# 4brar07_Audio_Amplifier.net
KiCad netlist of a schematic drawn in EAGLE
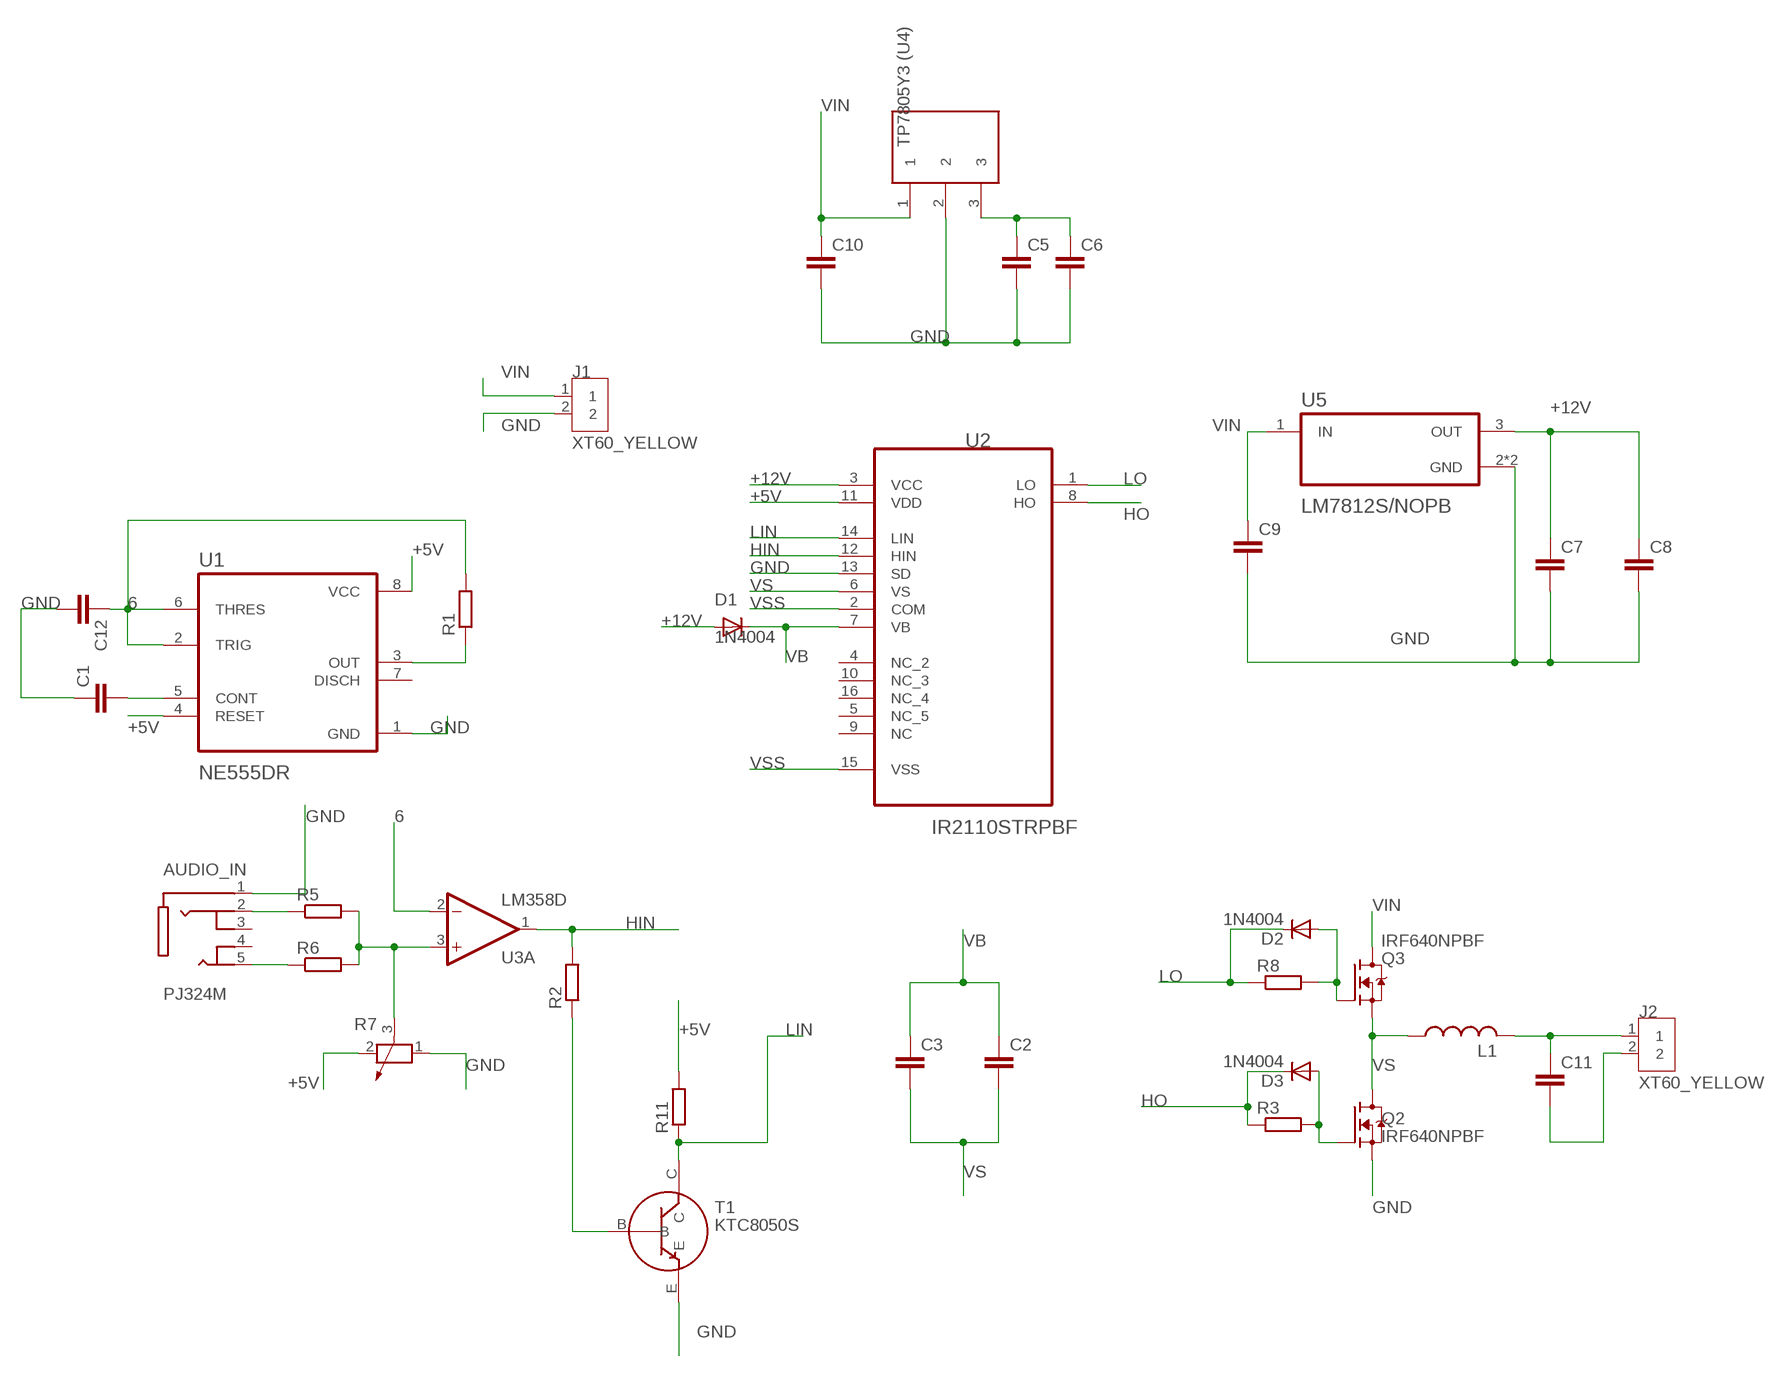
[diagram p0: schematic, sheet 1]

(export (version "E")
  (design (tool "Eeschema 10.0.6"))
  (components
    (comp (ref "AUDIO_IN")
      (value "PJ324M")
      (footprint "eagle-import:WENZHOU_PJ324M")
      (fields (field (name "MF") "Wenzhou QingPu Electronics Co.Ltd"))
      (libsource (lib "eagle-import") (part "PJ324M"))
    )
    (comp (ref "C1")
      (value "C-EU025-025X050")
      (footprint "eagle-import:C025-025X050")
      (libsource (lib "eagle-import") (part "C-EU025-025X050"))
    )
    (comp (ref "C2")
      (value "C-EU025-025X050")
      (footprint "eagle-import:C025-025X050")
      (libsource (lib "eagle-import") (part "C-EU025-025X050"))
    )
    (comp (ref "C3")
      (value "C-EU025-025X050")
      (footprint "eagle-import:C025-025X050")
      (libsource (lib "eagle-import") (part "C-EU025-025X050"))
    )
    (comp (ref "C5")
      (value "C-EU025-025X050")
      (footprint "eagle-import:C025-025X050")
      (libsource (lib "eagle-import") (part "C-EU025-025X050"))
    )
    (comp (ref "C6")
      (value "C-EU025-025X050")
      (footprint "eagle-import:C025-025X050")
      (libsource (lib "eagle-import") (part "C-EU025-025X050"))
    )
    (comp (ref "C7")
      (value "C-EU025-025X050")
      (footprint "eagle-import:C025-025X050")
      (libsource (lib "eagle-import") (part "C-EU025-025X050"))
    )
    (comp (ref "C8")
      (value "C-EU025-025X050")
      (footprint "eagle-import:C025-025X050")
      (libsource (lib "eagle-import") (part "C-EU025-025X050"))
    )
    (comp (ref "C9")
      (value "C-EU025-025X050")
      (footprint "eagle-import:C025-025X050")
      (libsource (lib "eagle-import") (part "C-EU025-025X050"))
    )
    (comp (ref "C10")
      (value "C-EU025-025X050")
      (footprint "eagle-import:C025-025X050")
      (libsource (lib "eagle-import") (part "C-EU025-025X050"))
    )
    (comp (ref "C11")
      (value "C-EU025-025X050")
      (footprint "eagle-import:C025-025X050")
      (libsource (lib "eagle-import") (part "C-EU025-025X050"))
    )
    (comp (ref "C12")
      (value "C-EU025-025X050")
      (footprint "eagle-import:C025-025X050")
      (libsource (lib "eagle-import") (part "C-EU025-025X050"))
    )
    (comp (ref "D1")
      (value "1N4004")
      (footprint "eagle-import:DO41-10")
      (libsource (lib "eagle-import") (part "1N4004"))
    )
    (comp (ref "D2")
      (value "1N4004")
      (footprint "eagle-import:DO41-10")
      (libsource (lib "eagle-import") (part "1N4004"))
    )
    (comp (ref "D3")
      (value "1N4004")
      (footprint "eagle-import:DO41-10")
      (libsource (lib "eagle-import") (part "1N4004"))
    )
    (comp (ref "J1")
      (value "XT60_YELLOW")
      (footprint "eagle-import:AMASS_XT60PB-M")
      (fields (field (name "MF") "Pololu") (field (name "MP") "XT60 YELLOW"))
      (libsource (lib "eagle-import") (part "XT60_YELLOW"))
    )
    (comp (ref "J2")
      (value "XT60_YELLOW")
      (footprint "eagle-import:AMASS_XT60PB-M")
      (fields (field (name "MF") "Pololu") (field (name "MP") "XT60 YELLOW"))
      (libsource (lib "eagle-import") (part "XT60_YELLOW"))
    )
    (comp (ref "L1")
      (value "L-US0207/10")
      (footprint "eagle-import:0207_10")
      (libsource (lib "eagle-import") (part "L-US0207/10"))
    )
    (comp (ref "Q2")
      (value "IRF640NPBF")
      (footprint "eagle-import:TO254P1067X483X2057-3")
      (fields (field (name "MF") "Infineon"))
      (libsource (lib "eagle-import") (part "IRF640NPBF"))
    )
    (comp (ref "Q3")
      (value "IRF640NPBF")
      (footprint "eagle-import:TO254P1067X483X2057-3")
      (fields (field (name "MF") "Infineon"))
      (libsource (lib "eagle-import") (part "IRF640NPBF"))
    )
    (comp (ref "R1")
      (value "R-EU_0204/7")
      (footprint "eagle-import:0204_7")
      (libsource (lib "eagle-import") (part "R-EU_0204/7"))
    )
    (comp (ref "R2")
      (value "R-EU_0204/7")
      (footprint "eagle-import:0204_7")
      (libsource (lib "eagle-import") (part "R-EU_0204/7"))
    )
    (comp (ref "R3")
      (value "R-EU_0204/7")
      (footprint "eagle-import:0204_7")
      (libsource (lib "eagle-import") (part "R-EU_0204/7"))
    )
    (comp (ref "R5")
      (value "R-EU_0204/7")
      (footprint "eagle-import:0204_7")
      (libsource (lib "eagle-import") (part "R-EU_0204/7"))
    )
    (comp (ref "R6")
      (value "R-EU_0204/7")
      (footprint "eagle-import:0204_7")
      (libsource (lib "eagle-import") (part "R-EU_0204/7"))
    )
    (comp (ref "R7")
      (value "POTENTIOMETER_PT-10")
      (footprint "eagle-import:PT-10")
      (libsource (lib "eagle-import") (part "POTENTIOMETER_PT-10"))
    )
    (comp (ref "R8")
      (value "R-EU_0204/7")
      (footprint "eagle-import:0204_7")
      (libsource (lib "eagle-import") (part "R-EU_0204/7"))
    )
    (comp (ref "R11")
      (value "R-EU_0204/7")
      (footprint "eagle-import:0204_7")
      (libsource (lib "eagle-import") (part "R-EU_0204/7"))
    )
    (comp (ref "T1")
      (value "KTC8050S")
      (footprint "eagle-import:KTC8050S")
      (libsource (lib "eagle-import") (part "KTC8050S"))
    )
    (comp (ref "TP7805Y3")
      (value "TP7805Y3")
      (footprint "eagle-import:TP7805Y3")
      (fields (field (name "TP7805Y3") "TP7805Y3 (U4)"))
      (libsource (lib "eagle-import") (part "TP7805Y3"))
    )
    (comp (ref "U1")
      (value "NE555DR")
      (footprint "eagle-import:SOIC127P599X175-8N")
      (fields (field (name "MF") "Texas Instruments"))
      (libsource (lib "eagle-import") (part "NE555DR"))
    )
    (comp (ref "U2")
      (value "IR2110STRPBF")
      (footprint "eagle-import:SOIC127P1032X265-16N")
      (fields (field (name "MF") "Infineon"))
      (libsource (lib "eagle-import") (part "IR2110STRPBF"))
    )
    (comp (ref "U3")
      (value "LM358D")
      (footprint "eagle-import:SO08")
      (libsource (lib "eagle-import") (part "LM358D"))
    )
    (comp (ref "U5")
      (value "LM7812S/NOPB")
      (footprint "eagle-import:TO254P1524X483-4N")
      (fields (field (name "MF") "Texas Instruments"))
      (libsource (lib "eagle-import") (part "LM7812S/NOPB"))
    )
  )
  (nets
    (net (code "1") (name "/+5V") (class "Default")
      (node (ref "R11") (pin "2") (pinfunction "2_2") (pintype "passive"))
      (node (ref "R7") (pin "2") (pinfunction "2_2") (pintype "passive"))
      (node (ref "U1") (pin "4") (pinfunction "RESET_4") (pintype "input"))
      (node (ref "U1") (pin "8") (pinfunction "VCC_8") (pintype "power_in"))
      (node (ref "U2") (pin "11") (pinfunction "VDD_11") (pintype "power_in"))
    )
    (net (code "2") (name "/+12V") (class "Default")
      (node (ref "C7") (pin "1") (pinfunction "1_1") (pintype "passive"))
      (node (ref "C8") (pin "1") (pinfunction "1_1") (pintype "passive"))
      (node (ref "D1") (pin "A") (pinfunction "A_A") (pintype "passive"))
      (node (ref "U2") (pin "3") (pinfunction "VCC_3") (pintype "power_in"))
      (node (ref "U5") (pin "3") (pinfunction "OUT_3") (pintype "output"))
    )
    (net (code "3") (name "/6") (class "Default")
      (node (ref "C12") (pin "1") (pinfunction "1_1") (pintype "passive"))
      (node (ref "R1") (pin "2") (pinfunction "2_2") (pintype "passive"))
      (node (ref "U1") (pin "2") (pinfunction "TRIG_2") (pintype "input"))
      (node (ref "U1") (pin "6") (pinfunction "THRES_6") (pintype "input"))
      (node (ref "U3") (pin "2") (pinfunction "-IN_2") (pintype "input"))
    )
    (net (code "4") (name "/GND") (class "Default")
      (node (ref "AUDIO_IN") (pin "1") (pinfunction "SLEEVE_1") (pintype "passive"))
      (node (ref "C1") (pin "1") (pinfunction "1_1") (pintype "passive"))
      (node (ref "C10") (pin "2") (pinfunction "2_2") (pintype "passive"))
      (node (ref "C12") (pin "2") (pinfunction "2_2") (pintype "passive"))
      (node (ref "C5") (pin "2") (pinfunction "2_2") (pintype "passive"))
      (node (ref "C6") (pin "2") (pinfunction "2_2") (pintype "passive"))
      (node (ref "C7") (pin "2") (pinfunction "2_2") (pintype "passive"))
      (node (ref "C8") (pin "2") (pinfunction "2_2") (pintype "passive"))
      (node (ref "C9") (pin "2") (pinfunction "2_2") (pintype "passive"))
      (node (ref "J1") (pin "2") (pinfunction "2_2") (pintype "passive"))
      (node (ref "Q2") (pin "3") (pinfunction "S_3") (pintype "passive"))
      (node (ref "R7") (pin "1") (pinfunction "1_1") (pintype "passive"))
      (node (ref "T1") (pin "E") (pinfunction "E_E") (pintype "bidirectional"))
      (node (ref "TP7805Y3") (pin "2") (pinfunction "2_2") (pintype "bidirectional"))
      (node (ref "U1") (pin "1") (pinfunction "GND_1") (pintype "power_in"))
      (node (ref "U2") (pin "13") (pinfunction "SD_13") (pintype "input"))
      (node (ref "U5") (pin "2") (pinfunction "GND_2") (pintype "power_in"))
      (node (ref "U5") (pin "4") (pinfunction "GND_4") (pintype "power_in"))
    )
    (net (code "5") (name "/HIN") (class "Default")
      (node (ref "R2") (pin "2") (pinfunction "2_2") (pintype "passive"))
      (node (ref "U2") (pin "12") (pinfunction "HIN_12") (pintype "input"))
      (node (ref "U3") (pin "1") (pinfunction "OUT_1") (pintype "output"))
    )
    (net (code "6") (name "/HO") (class "Default")
      (node (ref "D3") (pin "C") (pinfunction "C_C") (pintype "passive"))
      (node (ref "R3") (pin "1") (pinfunction "1_1") (pintype "passive"))
      (node (ref "U2") (pin "8") (pinfunction "HO_8") (pintype "output"))
    )
    (net (code "7") (name "/LIN") (class "Default")
      (node (ref "R11") (pin "1") (pinfunction "1_1") (pintype "passive"))
      (node (ref "T1") (pin "C") (pinfunction "C_C") (pintype "bidirectional"))
      (node (ref "U2") (pin "14") (pinfunction "LIN_14") (pintype "input"))
    )
    (net (code "8") (name "/LO") (class "Default")
      (node (ref "D2") (pin "C") (pinfunction "C_C") (pintype "passive"))
      (node (ref "R8") (pin "1") (pinfunction "1_1") (pintype "passive"))
      (node (ref "U2") (pin "1") (pinfunction "LO_1") (pintype "output"))
    )
    (net (code "9") (name "/VB") (class "Default")
      (node (ref "C2") (pin "1") (pinfunction "1_1") (pintype "passive"))
      (node (ref "C3") (pin "1") (pinfunction "1_1") (pintype "passive"))
      (node (ref "D1") (pin "C") (pinfunction "C_C") (pintype "passive"))
      (node (ref "U2") (pin "7") (pinfunction "VB_7") (pintype "input"))
    )
    (net (code "10") (name "/VIN") (class "Default")
      (node (ref "C10") (pin "1") (pinfunction "1_1") (pintype "passive"))
      (node (ref "C9") (pin "1") (pinfunction "1_1") (pintype "passive"))
      (node (ref "J1") (pin "1") (pinfunction "1_1") (pintype "passive"))
      (node (ref "Q3") (pin "2") (pinfunction "D_2") (pintype "passive"))
      (node (ref "TP7805Y3") (pin "1") (pinfunction "1_1") (pintype "bidirectional"))
      (node (ref "U5") (pin "1") (pinfunction "IN_1") (pintype "input"))
    )
    (net (code "11") (name "/VS") (class "Default")
      (node (ref "C2") (pin "2") (pinfunction "2_2") (pintype "passive"))
      (node (ref "C3") (pin "2") (pinfunction "2_2") (pintype "passive"))
      (node (ref "L1") (pin "1") (pinfunction "1_1") (pintype "passive"))
      (node (ref "Q2") (pin "2") (pinfunction "D_2") (pintype "passive"))
      (node (ref "Q3") (pin "3") (pinfunction "S_3") (pintype "passive"))
      (node (ref "U2") (pin "6") (pinfunction "VS_6") (pintype "input"))
    )
    (net (code "12") (name "/VSS") (class "Default")
      (node (ref "U2") (pin "15") (pinfunction "VSS_15") (pintype "passive"))
      (node (ref "U2") (pin "2") (pinfunction "COM_2") (pintype "input"))
    )
    (net (code "13") (name "Net-(AUDIO_IN-RING_1)") (class "Default")
      (node (ref "AUDIO_IN") (pin "2") (pinfunction "RING_1_2") (pintype "passive"))
      (node (ref "R5") (pin "1") (pinfunction "1_1") (pintype "passive"))
    )
    (net (code "14") (name "Net-(AUDIO_IN-TIP_2)") (class "Default")
      (node (ref "AUDIO_IN") (pin "5") (pinfunction "TIP_2_5") (pintype "passive"))
      (node (ref "R6") (pin "1") (pinfunction "1_1") (pintype "passive"))
    )
    (net (code "15") (name "Net-(C5-Pad1)") (class "Default")
      (node (ref "C5") (pin "1") (pinfunction "1_1") (pintype "passive"))
      (node (ref "C6") (pin "1") (pinfunction "1_1") (pintype "passive"))
      (node (ref "TP7805Y3") (pin "3") (pinfunction "3_3") (pintype "bidirectional"))
    )
    (net (code "16") (name "Net-(C11-Pad1)") (class "Default")
      (node (ref "C11") (pin "1") (pinfunction "1_1") (pintype "passive"))
      (node (ref "J2") (pin "1") (pinfunction "1_1") (pintype "passive"))
      (node (ref "L1") (pin "2") (pinfunction "2_2") (pintype "passive"))
    )
    (net (code "17") (name "Net-(C11-Pad2)") (class "Default")
      (node (ref "C11") (pin "2") (pinfunction "2_2") (pintype "passive"))
      (node (ref "J2") (pin "2") (pinfunction "2_2") (pintype "passive"))
    )
    (net (code "18") (name "Net-(Q2-G)") (class "Default")
      (node (ref "D3") (pin "A") (pinfunction "A_A") (pintype "passive"))
      (node (ref "Q2") (pin "1") (pinfunction "G_1") (pintype "passive"))
      (node (ref "R3") (pin "2") (pinfunction "2_2") (pintype "passive"))
    )
    (net (code "19") (name "Net-(Q3-G)") (class "Default")
      (node (ref "D2") (pin "A") (pinfunction "A_A") (pintype "passive"))
      (node (ref "Q3") (pin "1") (pinfunction "G_1") (pintype "passive"))
      (node (ref "R8") (pin "2") (pinfunction "2_2") (pintype "passive"))
    )
    (net (code "20") (name "Net-(R2-Pad1)") (class "Default")
      (node (ref "R2") (pin "1") (pinfunction "1_1") (pintype "passive"))
      (node (ref "T1") (pin "B") (pinfunction "B_B") (pintype "bidirectional"))
    )
    (net (code "21") (name "Net-(U1-CONT)") (class "Default")
      (node (ref "C1") (pin "2") (pinfunction "2_2") (pintype "passive"))
      (node (ref "U1") (pin "5") (pinfunction "CONT_5") (pintype "bidirectional"))
    )
    (net (code "22") (name "Net-(U1-OUT)") (class "Default")
      (node (ref "R1") (pin "1") (pinfunction "1_1") (pintype "passive"))
      (node (ref "U1") (pin "3") (pinfunction "OUT_3") (pintype "output"))
    )
    (net (code "23") (name "Net-(U3A-+IN)") (class "Default")
      (node (ref "R5") (pin "2") (pinfunction "2_2") (pintype "passive"))
      (node (ref "R6") (pin "2") (pinfunction "2_2") (pintype "passive"))
      (node (ref "R7") (pin "3") (pinfunction "3_3") (pintype "passive"))
      (node (ref "U3") (pin "3") (pinfunction "+IN_3") (pintype "input"))
    )
    (net (code "24") (name "unconnected-(AUDIO_IN-RING_2-Pad3)") (class "Default")
      (node (ref "AUDIO_IN") (pin "3") (pinfunction "RING_2_3") (pintype "passive"))
    )
    (net (code "25") (name "unconnected-(AUDIO_IN-TIP_1-Pad4)") (class "Default")
      (node (ref "AUDIO_IN") (pin "4") (pinfunction "TIP_1_4") (pintype "passive"))
    )
    (net (code "26") (name "unconnected-(U1-DISCH-Pad7)") (class "Default")
      (node (ref "U1") (pin "7") (pinfunction "DISCH_7") (pintype "output"))
    )
    (net (code "27") (name "unconnected-(U2-NC-Pad9)") (class "Default")
      (node (ref "U2") (pin "9") (pinfunction "NC_9") (pintype "no_connect"))
    )
    (net (code "28") (name "unconnected-(U2-NC_2-Pad4)") (class "Default")
      (node (ref "U2") (pin "4") (pinfunction "NC_2_4") (pintype "no_connect"))
    )
    (net (code "29") (name "unconnected-(U2-NC_3-Pad10)") (class "Default")
      (node (ref "U2") (pin "10") (pinfunction "NC_3_10") (pintype "no_connect"))
    )
    (net (code "30") (name "unconnected-(U2-NC_4-Pad16)") (class "Default")
      (node (ref "U2") (pin "16") (pinfunction "NC_4_16") (pintype "no_connect"))
    )
    (net (code "31") (name "unconnected-(U2-NC_5-Pad5)") (class "Default")
      (node (ref "U2") (pin "5") (pinfunction "NC_5_5") (pintype "no_connect"))
    )
  )
)
